# 12V_3V3_1V8_Swiches.net
KiCad netlist of a schematic drawn in Altium Designer
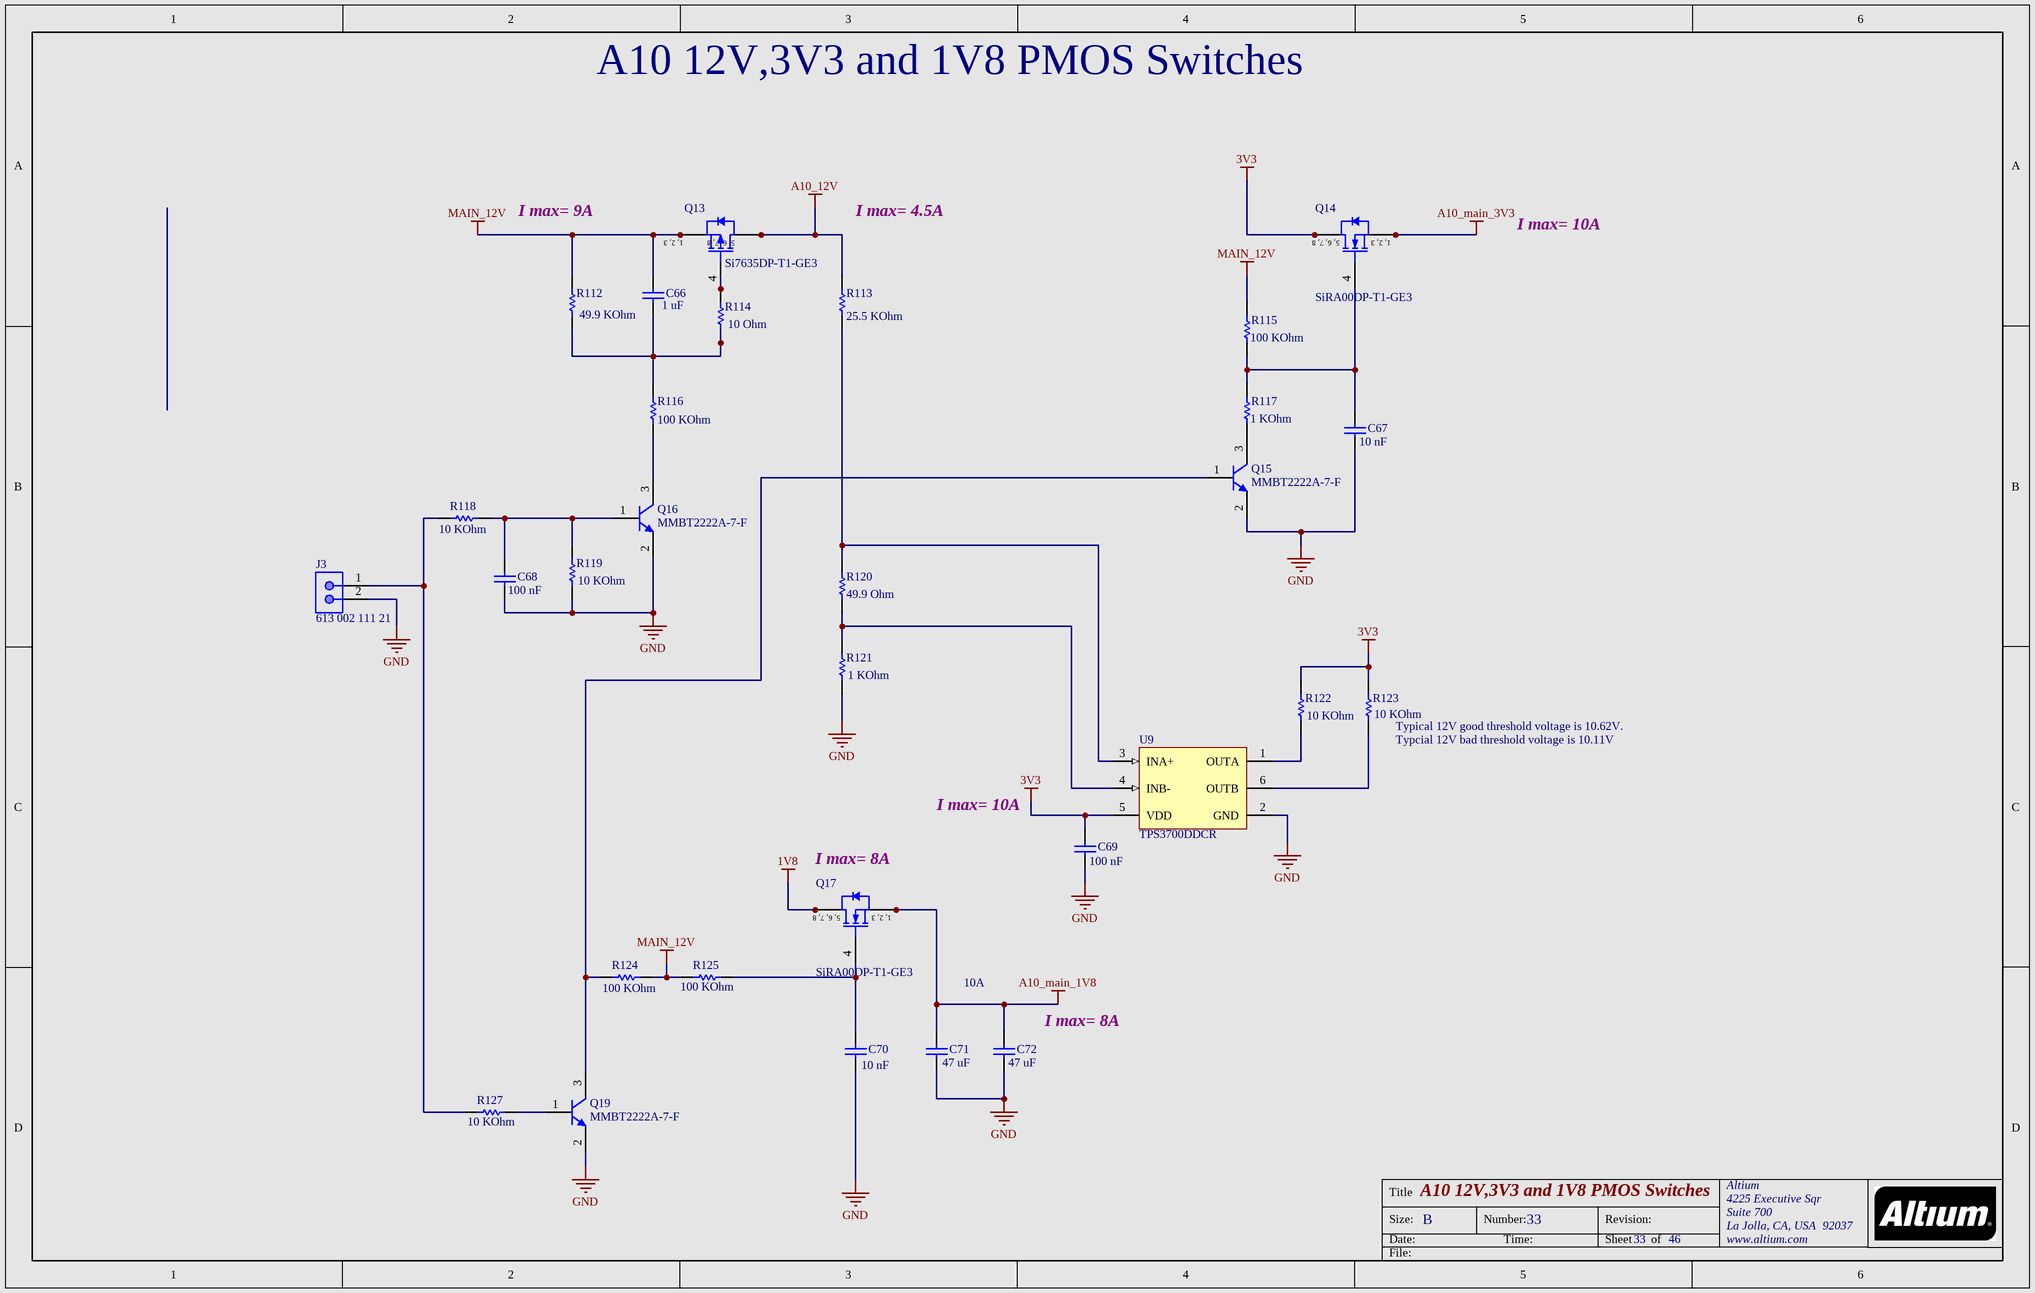
[diagram p0: 12V_3V3_1V8_Swiches.SchDoc]

(export (version "E")
  (design (tool "Eeschema 10.0.6"))
  (components
    (comp (ref "C66")
      (value "CGB2A1X5R1E105K033BC")
      (footprint "CAPC1005X33X10LL5")
      (description "Chip Capacitor, 1 uF, +/- 10%, 25 V, -55 to 85 degC, 0402 (1005 Metric), RoHS, Tape and Reel")
      (fields (field (name "TOLERANCE") "10%") (field (name "CAPACITANCE") "1 uF"))
      (libsource (lib "") (part "CAP-NP-2_1"))
    )
    (comp (ref "C67")
      (value "GRM155R71H103KA88D")
      (footprint "CAPC1005X55X25ML05T10")
      (description "Chip Capacitor, 10 nF, +/- 10%, 50 V, -55 to 125 degC, 0402 (1005 Metric), RoHS, Tape and Reel")
      (fields
        (field (name "TOLERANCE") "10%")
        (field (name "CAPACITANCE") "10 nF")
        (field (name "MANUFACTURER") "Basic Passives")
      )
      (libsource (lib "Altium Content Vault") (part "CAP-NP-2"))
    )
    (comp (ref "C68")
      (value "C1005X7R1E104M")
      (footprint "CAPC1005X55X10LL05")
      (description "Chip Capacitor, 0.1 uF, +/- 20%, 25 V, -55 to 125 degC, 0402 (1005 Metric), RoHS, Tape and Reel")
      (fields (field (name "TOLERANCE") "20%") (field (name "CAPACITANCE") "100 nF"))
      (libsource (lib "Altium Content Vault") (part "CAP-NP-2"))
    )
    (comp (ref "C69")
      (value "C1005X7R1E104M")
      (footprint "CAPC1005X55X10LL05")
      (description "Chip Capacitor, 0.1 uF, +/- 20%, 25 V, -55 to 125 degC, 0402 (1005 Metric), RoHS, Tape and Reel")
      (fields (field (name "TOLERANCE") "20%") (field (name "CAPACITANCE") "100 nF"))
      (libsource (lib "Altium Content Vault") (part "CAP-NP-2"))
    )
    (comp (ref "C70")
      (value "GRM155R71H103KA88D")
      (footprint "CAPC1005X55X25ML05T10")
      (description "Chip Capacitor, 10 nF, +/- 10%, 50 V, -55 to 125 degC, 0402 (1005 Metric), RoHS, Tape and Reel")
      (fields
        (field (name "TOLERANCE") "10%")
        (field (name "CAPACITANCE") "10 nF")
        (field (name "MANUFACTURER") "Basic Passives")
      )
      (libsource (lib "Altium Content Vault") (part "CAP-NP-2"))
    )
    (comp (ref "C71")
      (value "C3216X5R1A476M160AB")
      (footprint "CAPC3216X180X20ML20")
      (description "Chip Capacitor, 47 uF, +/- 20%, 10 V, -55 to 85 degC, 1206 (3216 Metric), RoHS, Tape and Reel")
      (fields (field (name "TOLERANCE") "20%") (field (name "CAPACITANCE") "47 uF"))
      (libsource (lib "") (part "CAP-NP-2_1"))
    )
    (comp (ref "C72")
      (value "C3216X5R1A476M160AB")
      (footprint "CAPC3216X180X20ML20")
      (description "Chip Capacitor, 47 uF, +/- 20%, 10 V, -55 to 85 degC, 1206 (3216 Metric), RoHS, Tape and Reel")
      (fields (field (name "TOLERANCE") "20%") (field (name "CAPACITANCE") "47 uF"))
      (libsource (lib "") (part "CAP-NP-2_1"))
    )
    (comp (ref "J3")
      (value "613 002 111 21")
      (footprint "WE-61300211121_V")
      (fields (field (name "MANUFACTURER") "Wuerth Elektronik"))
      (libsource (lib "Altium Content Vault") (part "CMP-1712-00002-1"))
    )
    (comp (ref "Q13")
      (value "Si7635DP-T1-GE3")
      (footprint "VISH-PPAKSO-8_V")
      (description "P-Channel MOSFET, 20 V, -55 to 150 degC, 8-Pin SMD (PPAKSO-8), RoHS, Tape and Reel")
      (libsource (lib "Altium Content Vault") (part "PEMOS-SSSGDDDD-8"))
    )
    (comp (ref "Q14")
      (value "SiRA00DP-T1-GE3")
      (footprint "VISH-PPAKSO-8_V")
      (description "N-Channe MOSFET, 30 V, -55 to 150 degC, 8-Pin SMD (PPAKSO-8), RoHS, Tape and Reel")
      (libsource (lib "Altium Content Vault") (part "NEMOS-SSSGDDDD-8"))
    )
    (comp (ref "Q15")
      (value "MMBT2222A-7-F")
      (footprint "DIOD-SOT23-3_V")
      (description "NPN Small Signal Transistor, 40 V, -55 to 150 degC, 3-Pin SOT23, RoHS, Tape and Reel")
      (fields (field (name "MANUFACTURER") "Diodes Inc"))
      (libsource (lib "Altium Content Vault") (part "BJT-NPN-BEC-3"))
    )
    (comp (ref "Q16")
      (value "MMBT2222A-7-F")
      (footprint "DIOD-SOT23-3_V")
      (description "NPN Small Signal Transistor, 40 V, -55 to 150 degC, 3-Pin SOT23, RoHS, Tape and Reel")
      (fields (field (name "MANUFACTURER") "Diodes Inc"))
      (libsource (lib "Altium Content Vault") (part "BJT-NPN-BEC-3"))
    )
    (comp (ref "Q17")
      (value "SiRA00DP-T1-GE3")
      (footprint "VISH-PPAKSO-8_V")
      (description "N-Channe MOSFET, 30 V, -55 to 150 degC, 8-Pin SMD (PPAKSO-8), RoHS, Tape and Reel")
      (libsource (lib "Altium Content Vault") (part "NEMOS-SSSGDDDD-8"))
    )
    (comp (ref "Q19")
      (value "MMBT2222A-7-F")
      (footprint "DIOD-SOT23-3_V")
      (description "NPN Small Signal Transistor, 40 V, -55 to 150 degC, 3-Pin SOT23, RoHS, Tape and Reel")
      (fields (field (name "MANUFACTURER") "Diodes Inc"))
      (libsource (lib "Altium Content Vault") (part "BJT-NPN-BEC-3"))
    )
    (comp (ref "R112")
      (value "CMP-2002-00967")
      (footprint "RESC1005X40X25ML05T05")
      (description "Chip Resistor, 49.9 KOhm, +/- 1%, 100 mW, -55 to 155 degC, 0402 (1005 Metric), RoHS, Tape and Reel")
      (fields
        (field (name "PARTNUMBER") "ERJ-2RKF4992X")
        (field (name "TOLERANCE") "1%")
        (field (name "RESISTANCE") "49.9 KOhm")
      )
      (libsource (lib "Altium Content Vault") (part "CMP-2002-00967-2"))
    )
    (comp (ref "R113")
      (value "ERJ-2RKF2552x")
      (footprint "RESC1005X40X25NL05T05")
      (description "Chip Resistor, 25.5 KOhm, +/- 1%, 100 mW, -55 to 155 degC, 0402 (1005 Metric), RoHS, Tape and Reel")
      (fields (field (name "RESISTANCE") "25.5 KOhm") (field (name "TOLERANCE") "1%"))
      (libsource (lib "") (part "RES-2_1"))
    )
    (comp (ref "R114")
      (value "ERJ-2RKF10R0X")
      (footprint "RESC1005X40X25LL05T05")
      (description "Chip Resistor, 10 Ohm, +/- 1%, 100 mW, -55 to 155 degC, 0402 (1005 Metric), RoHS, Tape and Reel")
      (fields
        (field (name "RESISTANCE") "10 Ohm")
        (field (name "TOLERANCE") "1%")
        (field (name "MANUFACTURER") "Basic Passives")
      )
      (libsource (lib "Altium Content Vault") (part "RES-2"))
    )
    (comp (ref "R115")
      (value "ERJ-2RKF1003X")
      (footprint "RESC1005X40X25LL05T05")
      (description "Chip Resistor, 100 KOhm, +/- 1%, 100 mW, -55 to 155 degC, 0402 (1005 Metric), RoHS, Tape and Reel")
      (fields
        (field (name "RESISTANCE") "100 KOhm")
        (field (name "TOLERANCE") "1%")
        (field (name "MANUFACTURER") "Basic Passives")
      )
      (libsource (lib "Altium Content Vault") (part "RES-2"))
    )
    (comp (ref "R116")
      (value "ERJ-2RKF1003X")
      (footprint "RESC1005X40X25LL05T05")
      (description "Chip Resistor, 100 KOhm, +/- 1%, 100 mW, -55 to 155 degC, 0402 (1005 Metric), RoHS, Tape and Reel")
      (fields
        (field (name "RESISTANCE") "100 KOhm")
        (field (name "TOLERANCE") "1%")
        (field (name "MANUFACTURER") "Basic Passives")
      )
      (libsource (lib "Altium Content Vault") (part "RES-2"))
    )
    (comp (ref "R117")
      (value "ERJ-2RKF1001X")
      (footprint "RESC1005X40X25LL05T05")
      (description "Chip Resistor, 1 KOhm, +/- 1%, 100 mW, -55 to 155 degC, 0402 (1005 Metric), RoHS, Tape and Reel")
      (fields
        (field (name "RESISTANCE") "1 KOhm")
        (field (name "TOLERANCE") "1%")
        (field (name "MANUFACTURER") "Basic Passives")
      )
      (libsource (lib "Altium Content Vault") (part "RES-2"))
    )
    (comp (ref "R118")
      (value "ERJ-2RKF1002X")
      (footprint "RESC1005X40X25NL05T05")
      (description "Chip Resistor, 10 KOhm, +/- 1%, 100 mW, -55 to 155 degC, 0402 (1005 Metric), RoHS, Tape and Reel")
      (fields
        (field (name "TOLERANCE") "1%")
        (field (name "RESISTANCE") "10 KOhm")
        (field (name "MANUFACTURER") "Basic Passives")
      )
      (libsource (lib "Altium Content Vault") (part "RES-2"))
    )
    (comp (ref "R119")
      (value "ERJ-2RKF1002X")
      (footprint "RESC1005X40X25NL05T05")
      (description "Chip Resistor, 10 KOhm, +/- 1%, 100 mW, -55 to 155 degC, 0402 (1005 Metric), RoHS, Tape and Reel")
      (fields
        (field (name "TOLERANCE") "1%")
        (field (name "RESISTANCE") "10 KOhm")
        (field (name "MANUFACTURER") "Basic Passives")
      )
      (libsource (lib "Altium Content Vault") (part "RES-2"))
    )
    (comp (ref "R120")
      (value "NRC04F49R9TRF")
      (footprint "RESC1005X35X25NL8T10")
      (description "Chip Resistor, 49.9 Ohm, +/- 1%, 0.06 W, -55 to 155 degC, 0402 (1005 Metric), RoHS, Tape and Reel")
      (fields (field (name "TOLERANCE") "1%") (field (name "RESISTANCE") "49.9 Ohm"))
      (libsource (lib "Altium Content Vault") (part "CMP-1599-00001-2"))
    )
    (comp (ref "R121")
      (value "ERJ-2RKF1001X")
      (footprint "RESC1005X40X25LL05T05")
      (description "Chip Resistor, 1 KOhm, +/- 1%, 100 mW, -55 to 155 degC, 0402 (1005 Metric), RoHS, Tape and Reel")
      (fields
        (field (name "RESISTANCE") "1 KOhm")
        (field (name "TOLERANCE") "1%")
        (field (name "MANUFACTURER") "Basic Passives")
      )
      (libsource (lib "Altium Content Vault") (part "RES-2"))
    )
    (comp (ref "R122")
      (value "ERJ-2RKF1002X")
      (footprint "RESC1005X40X25NL05T05")
      (description "Chip Resistor, 10 KOhm, +/- 1%, 100 mW, -55 to 155 degC, 0402 (1005 Metric), RoHS, Tape and Reel")
      (fields
        (field (name "TOLERANCE") "1%")
        (field (name "RESISTANCE") "10 KOhm")
        (field (name "MANUFACTURER") "Basic Passives")
      )
      (libsource (lib "Altium Content Vault") (part "RES-2"))
    )
    (comp (ref "R123")
      (value "ERJ-2RKF1002X")
      (footprint "RESC1005X40X25NL05T05")
      (description "Chip Resistor, 10 KOhm, +/- 1%, 100 mW, -55 to 155 degC, 0402 (1005 Metric), RoHS, Tape and Reel")
      (fields
        (field (name "TOLERANCE") "1%")
        (field (name "RESISTANCE") "10 KOhm")
        (field (name "MANUFACTURER") "Basic Passives")
      )
      (libsource (lib "Altium Content Vault") (part "RES-2"))
    )
    (comp (ref "R124")
      (value "ERJ-2RKF1003X")
      (footprint "RESC1005X40X25LL05T05")
      (description "Chip Resistor, 100 KOhm, +/- 1%, 100 mW, -55 to 155 degC, 0402 (1005 Metric), RoHS, Tape and Reel")
      (fields
        (field (name "RESISTANCE") "100 KOhm")
        (field (name "TOLERANCE") "1%")
        (field (name "MANUFACTURER") "Basic Passives")
      )
      (libsource (lib "Altium Content Vault") (part "RES-2"))
    )
    (comp (ref "R125")
      (value "ERJ-2RKF1003X")
      (footprint "RESC1005X40X25LL05T05")
      (description "Chip Resistor, 100 KOhm, +/- 1%, 100 mW, -55 to 155 degC, 0402 (1005 Metric), RoHS, Tape and Reel")
      (fields
        (field (name "RESISTANCE") "100 KOhm")
        (field (name "TOLERANCE") "1%")
        (field (name "MANUFACTURER") "Basic Passives")
      )
      (libsource (lib "Altium Content Vault") (part "RES-2"))
    )
    (comp (ref "R127")
      (value "ERJ-2RKF1002X")
      (footprint "RESC1005X40X25NL05T05")
      (description "Chip Resistor, 10 KOhm, +/- 1%, 100 mW, -55 to 155 degC, 0402 (1005 Metric), RoHS, Tape and Reel")
      (fields
        (field (name "TOLERANCE") "1%")
        (field (name "RESISTANCE") "10 KOhm")
        (field (name "MANUFACTURER") "Basic Passives")
      )
      (libsource (lib "Altium Content Vault") (part "RES-2"))
    )
    (comp (ref "U9")
      (value "TPS3700DDCR")
      (footprint "DDC0006A_M")
      (libsource (lib "Altium Content Vault") (part "TI-TPS3700-DDC6"))
    )
  )
  (nets
    (net (code "1") (name "1V8") (class "Default")
      (node (ref "Q17") (pin "5") (pinfunction "D_5") (pintype "passive"))
      (node (ref "Q17") (pin "6") (pinfunction "D_6") (pintype "passive"))
      (node (ref "Q17") (pin "7") (pinfunction "D_7") (pintype "passive"))
      (node (ref "Q17") (pin "8") (pinfunction "D_8") (pintype "passive"))
    )
    (net (code "2") (name "3V3") (class "Default")
      (node (ref "C69") (pin "2") (pinfunction "2_2") (pintype "passive"))
      (node (ref "Q14") (pin "5") (pinfunction "D_5") (pintype "passive"))
      (node (ref "Q14") (pin "6") (pinfunction "D_6") (pintype "passive"))
      (node (ref "Q14") (pin "7") (pinfunction "D_7") (pintype "passive"))
      (node (ref "Q14") (pin "8") (pinfunction "D_8") (pintype "passive"))
      (node (ref "R122") (pin "1") (pinfunction "1_1") (pintype "passive"))
      (node (ref "R123") (pin "1") (pinfunction "1_1") (pintype "passive"))
      (node (ref "U9") (pin "5") (pinfunction "VDD_5") (pintype "power_in"))
    )
    (net (code "3") (name "A10_12V") (class "Default")
      (node (ref "Q13") (pin "5") (pinfunction "D_5") (pintype "passive"))
      (node (ref "Q13") (pin "6") (pinfunction "D_6") (pintype "passive"))
      (node (ref "Q13") (pin "7") (pinfunction "D_7") (pintype "passive"))
      (node (ref "Q13") (pin "8") (pinfunction "D_8") (pintype "passive"))
      (node (ref "R113") (pin "2") (pinfunction "2_2") (pintype "passive"))
    )
    (net (code "4") (name "A10_main_1V8") (class "Default")
      (node (ref "C71") (pin "2") (pinfunction "2_2") (pintype "passive"))
      (node (ref "C72") (pin "2") (pinfunction "2_2") (pintype "passive"))
      (node (ref "Q17") (pin "1") (pinfunction "S_1") (pintype "passive"))
      (node (ref "Q17") (pin "2") (pinfunction "S_2") (pintype "passive"))
      (node (ref "Q17") (pin "3") (pinfunction "S_3") (pintype "passive"))
    )
    (net (code "5") (name "A10_main_3V3") (class "Default")
      (node (ref "Q14") (pin "1") (pinfunction "S_1") (pintype "passive"))
      (node (ref "Q14") (pin "2") (pinfunction "S_2") (pintype "passive"))
      (node (ref "Q14") (pin "3") (pinfunction "S_3") (pintype "passive"))
    )
    (net (code "6") (name "GND") (class "Default")
      (node (ref "C67") (pin "1") (pinfunction "1_1") (pintype "passive"))
      (node (ref "C68") (pin "1") (pinfunction "1_1") (pintype "passive"))
      (node (ref "C69") (pin "1") (pinfunction "1_1") (pintype "passive"))
      (node (ref "C70") (pin "1") (pinfunction "1_1") (pintype "passive"))
      (node (ref "C71") (pin "1") (pinfunction "1_1") (pintype "passive"))
      (node (ref "C72") (pin "1") (pinfunction "1_1") (pintype "passive"))
      (node (ref "J3") (pin "2") (pinfunction "2_2") (pintype "passive"))
      (node (ref "Q15") (pin "2") (pinfunction "E_2") (pintype "passive"))
      (node (ref "Q16") (pin "2") (pinfunction "E_2") (pintype "passive"))
      (node (ref "Q19") (pin "2") (pinfunction "E_2") (pintype "passive"))
      (node (ref "R119") (pin "1") (pinfunction "1_1") (pintype "passive"))
      (node (ref "R121") (pin "1") (pinfunction "1_1") (pintype "passive"))
      (node (ref "U9") (pin "2") (pinfunction "GND_2") (pintype "power_in"))
    )
    (net (code "7") (name "MAIN_12V") (class "Default")
      (node (ref "C66") (pin "2") (pinfunction "2_2") (pintype "passive"))
      (node (ref "Q13") (pin "1") (pinfunction "S_1") (pintype "passive"))
      (node (ref "Q13") (pin "2") (pinfunction "S_2") (pintype "passive"))
      (node (ref "Q13") (pin "3") (pinfunction "S_3") (pintype "passive"))
      (node (ref "R112") (pin "2") (pinfunction "2_2") (pintype "passive"))
      (node (ref "R115") (pin "2") (pinfunction "2_2") (pintype "passive"))
      (node (ref "R124") (pin "1") (pinfunction "1_1") (pintype "passive"))
      (node (ref "R125") (pin "2") (pinfunction "2_2") (pintype "passive"))
    )
    (net (code "8") (name "Net-(C66-Pad1)") (class "Default")
      (node (ref "C66") (pin "1") (pinfunction "1_1") (pintype "passive"))
      (node (ref "R112") (pin "1") (pinfunction "1_1") (pintype "passive"))
      (node (ref "R114") (pin "1") (pinfunction "1_1") (pintype "passive"))
      (node (ref "R116") (pin "2") (pinfunction "2_2") (pintype "passive"))
    )
    (net (code "9") (name "Net-(J3-Pad1)") (class "Default")
      (node (ref "J3") (pin "1") (pinfunction "1_1") (pintype "passive"))
      (node (ref "R118") (pin "2") (pinfunction "2_2") (pintype "passive"))
      (node (ref "R127") (pin "2") (pinfunction "2_2") (pintype "passive"))
    )
    (net (code "10") (name "Net-(Q13-G)") (class "Default")
      (node (ref "Q13") (pin "4") (pinfunction "G_4") (pintype "passive"))
      (node (ref "R114") (pin "2") (pinfunction "2_2") (pintype "passive"))
    )
    (net (code "11") (name "Net-(Q14-G)") (class "Default")
      (node (ref "C67") (pin "2") (pinfunction "2_2") (pintype "passive"))
      (node (ref "Q14") (pin "4") (pinfunction "G_4") (pintype "passive"))
      (node (ref "R115") (pin "1") (pinfunction "1_1") (pintype "passive"))
      (node (ref "R117") (pin "2") (pinfunction "2_2") (pintype "passive"))
    )
    (net (code "12") (name "Net-(Q15-B)") (class "Default")
      (node (ref "Q15") (pin "1") (pinfunction "B_1") (pintype "passive"))
      (node (ref "Q19") (pin "3") (pinfunction "C_3") (pintype "passive"))
      (node (ref "R124") (pin "2") (pinfunction "2_2") (pintype "passive"))
    )
    (net (code "13") (name "Net-(Q15-C)") (class "Default")
      (node (ref "Q15") (pin "3") (pinfunction "C_3") (pintype "passive"))
      (node (ref "R117") (pin "1") (pinfunction "1_1") (pintype "passive"))
    )
    (net (code "14") (name "Net-(Q16-B)") (class "Default")
      (node (ref "C68") (pin "2") (pinfunction "2_2") (pintype "passive"))
      (node (ref "Q16") (pin "1") (pinfunction "B_1") (pintype "passive"))
      (node (ref "R118") (pin "1") (pinfunction "1_1") (pintype "passive"))
      (node (ref "R119") (pin "2") (pinfunction "2_2") (pintype "passive"))
    )
    (net (code "15") (name "Net-(Q16-C)") (class "Default")
      (node (ref "Q16") (pin "3") (pinfunction "C_3") (pintype "passive"))
      (node (ref "R116") (pin "1") (pinfunction "1_1") (pintype "passive"))
    )
    (net (code "16") (name "Net-(Q17-G)") (class "Default")
      (node (ref "C70") (pin "2") (pinfunction "2_2") (pintype "passive"))
      (node (ref "Q17") (pin "4") (pinfunction "G_4") (pintype "passive"))
      (node (ref "R125") (pin "1") (pinfunction "1_1") (pintype "passive"))
    )
    (net (code "17") (name "Net-(Q19-B)") (class "Default")
      (node (ref "Q19") (pin "1") (pinfunction "B_1") (pintype "passive"))
      (node (ref "R127") (pin "1") (pinfunction "1_1") (pintype "passive"))
    )
    (net (code "18") (name "Net-(U9-INA+)") (class "Default")
      (node (ref "R113") (pin "1") (pinfunction "1_1") (pintype "passive"))
      (node (ref "R120") (pin "2") (pinfunction "2_2") (pintype "passive"))
      (node (ref "U9") (pin "3") (pinfunction "INA+_3") (pintype "input"))
    )
    (net (code "19") (name "Net-(U9-INB-)") (class "Default")
      (node (ref "R120") (pin "1") (pinfunction "1_1") (pintype "passive"))
      (node (ref "R121") (pin "2") (pinfunction "2_2") (pintype "passive"))
      (node (ref "U9") (pin "4") (pinfunction "INB-_4") (pintype "input"))
    )
    (net (code "20") (name "Net-(U9-OUTA)") (class "Default")
      (node (ref "R122") (pin "2") (pinfunction "2_2") (pintype "passive"))
      (node (ref "U9") (pin "1") (pinfunction "OUTA_1") (pintype "open_collector"))
    )
    (net (code "21") (name "Net-(U9-OUTB)") (class "Default")
      (node (ref "R123") (pin "2") (pinfunction "2_2") (pintype "passive"))
      (node (ref "U9") (pin "6") (pinfunction "OUTB_6") (pintype "open_collector"))
    )
  )
)
